# ESP32__20241002.net
KiCad netlist of a schematic drawn in Altium Designer
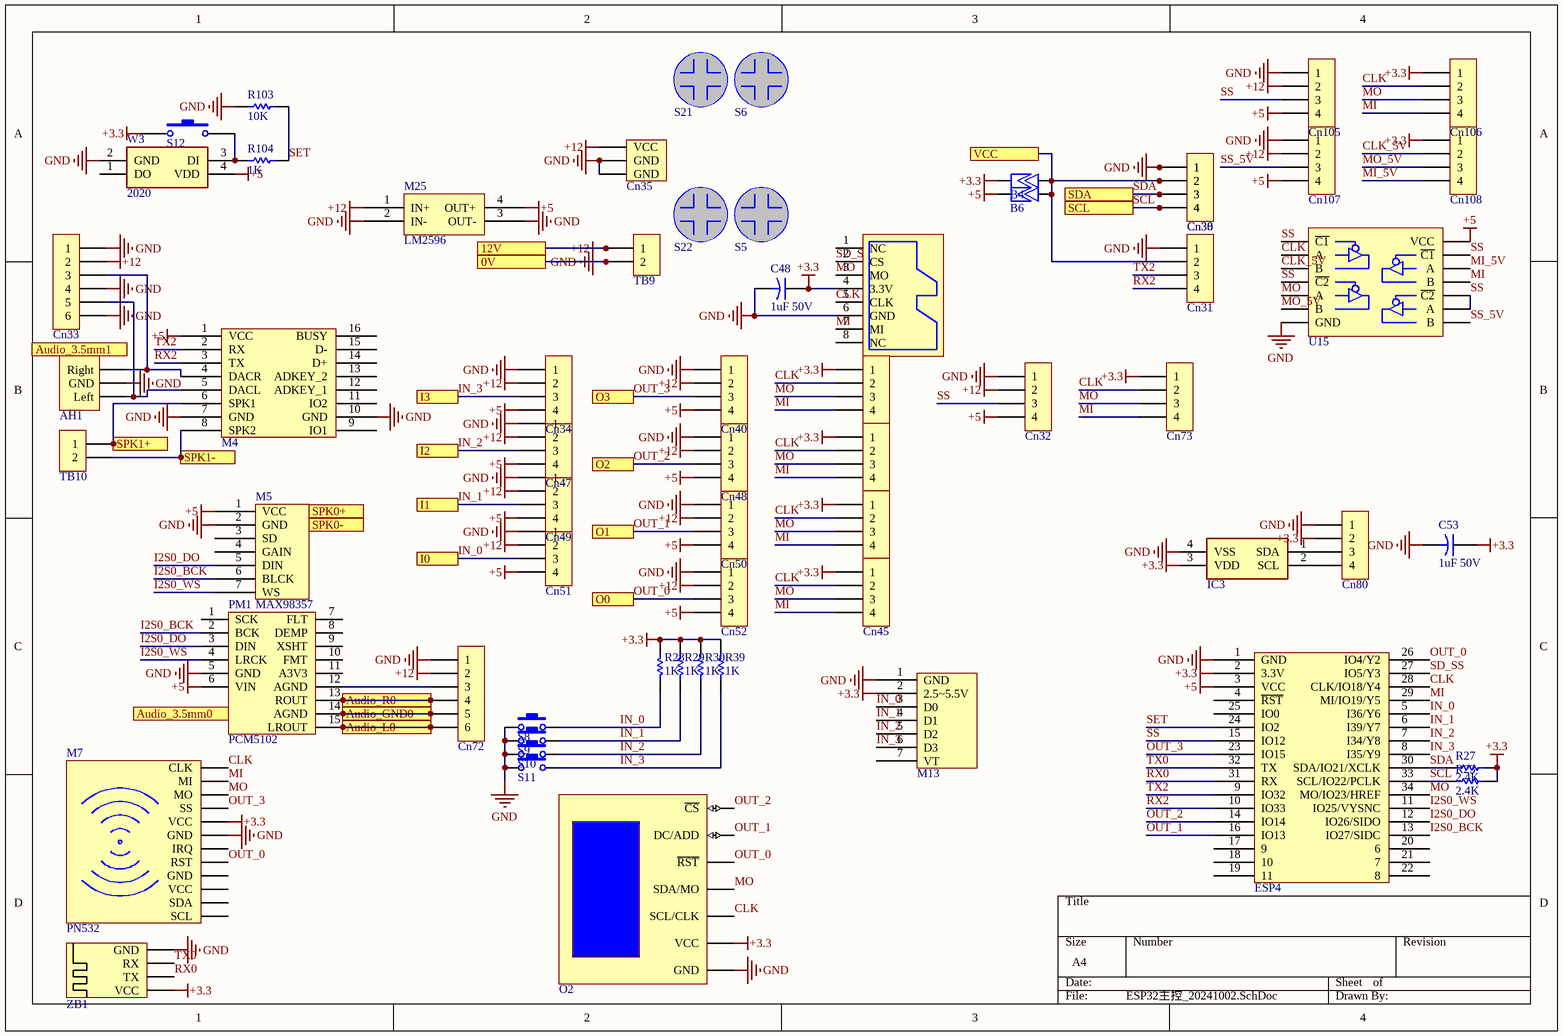
[diagram p0: ESP32主控_20241002.SchDoc]

(export (version "E")
  (design (tool "Eeschema 10.0.6"))
  (components
    (comp (ref "AH1")
      (value "Interface_Audio_hole")
      (footprint "Audio_hole_DIP")
      (description "音源孔")
      (libsource (lib "MyLibray") (part "Interface_Audio_hole"))
    )
    (comp (ref "B4")
      (value "短路")
      (footprint "BYPASS-0805")
      (description "短路焊點(如標註短路則需額外補錫使其短路)")
      (libsource (lib "MyLibray") (part "Bypass"))
    )
    (comp (ref "B6")
      (value "不短路")
      (footprint "BYPASS-0805")
      (description "短路焊點(如標註短路則需額外補錫使其短路)")
      (libsource (lib "MyLibray") (part "Bypass"))
    )
    (comp (ref "C48")
      (value "1uF 50V")
      (footprint "Cap-1206")
      (description "電容")
      (libsource (lib "MyLibray") (part "Cap"))
    )
    (comp (ref "C53")
      (value "1uF 50V")
      (footprint "Cap-1206")
      (description "電容")
      (libsource (lib "MyLibray") (part "Cap"))
    )
    (comp (ref "Cn28")
      (value "KF2510")
      (footprint "Connector_KF2510-4A")
      (description "接線端子")
      (libsource (lib "MyLibray") (part "Contact(4P)"))
    )
    (comp (ref "Cn29")
      (value "KF2510")
      (footprint "Connector_KF2510-4A")
      (description "接線端子")
      (libsource (lib "MyLibray") (part "Contact(4P)"))
    )
    (comp (ref "Cn30")
      (value "KF2510")
      (footprint "Connector_KF2510-4A")
      (description "接線端子")
      (libsource (lib "MyLibray") (part "Contact(4P)"))
    )
    (comp (ref "Cn31")
      (value "KF2510")
      (footprint "Connector_KF2510-4A")
      (description "接線端子")
      (libsource (lib "MyLibray") (part "Contact(4P)"))
    )
    (comp (ref "Cn32")
      (value "KF2510")
      (footprint "Connector_KF2510-4A")
      (description "接線端子")
      (libsource (lib "MyLibray") (part "Contact(4P)"))
    )
    (comp (ref "Cn33")
      (value "KF2510-6")
      (footprint "Connector_KF2510-6W")
      (description "接線端子")
      (libsource (lib "") (part "Contact(6P)_1"))
    )
    (comp (ref "Cn34")
      (value "KF2510")
      (footprint "Connector_KF2510-4A")
      (description "接線端子")
      (libsource (lib "MyLibray") (part "Contact(4P)"))
    )
    (comp (ref "Cn35")
      (value "DC-005")
      (footprint "Connector_DC-005")
      (description "DC直流接頭")
      (libsource (lib "MyLibray") (part "Contact_DC"))
    )
    (comp (ref "Cn38")
      (value "KF2510")
      (footprint "Connector_KF2510-4A")
      (description "接線端子")
      (libsource (lib "MyLibray") (part "Contact(4P)"))
    )
    (comp (ref "Cn40")
      (value "KF2510")
      (footprint "Connector_KF2510-4A")
      (description "接線端子")
      (libsource (lib "MyLibray") (part "Contact(4P)"))
    )
    (comp (ref "Cn43")
      (value "KF2510")
      (footprint "Connector_KF2510-4A")
      (description "接線端子")
      (libsource (lib "MyLibray") (part "Contact(4P)"))
    )
    (comp (ref "Cn45")
      (value "KF2510")
      (footprint "Connector_KF2510-4A")
      (description "接線端子")
      (libsource (lib "MyLibray") (part "Contact(4P)"))
    )
    (comp (ref "Cn47")
      (value "KF2510")
      (footprint "Connector_KF2510-4A")
      (description "接線端子")
      (libsource (lib "MyLibray") (part "Contact(4P)"))
    )
    (comp (ref "Cn48")
      (value "KF2510")
      (footprint "Connector_KF2510-4A")
      (description "接線端子")
      (libsource (lib "MyLibray") (part "Contact(4P)"))
    )
    (comp (ref "Cn49")
      (value "KF2510")
      (footprint "Connector_KF2510-4A")
      (description "接線端子")
      (libsource (lib "MyLibray") (part "Contact(4P)"))
    )
    (comp (ref "Cn50")
      (value "KF2510")
      (footprint "Connector_KF2510-4A")
      (description "接線端子")
      (libsource (lib "MyLibray") (part "Contact(4P)"))
    )
    (comp (ref "Cn51")
      (value "KF2510")
      (footprint "Connector_KF2510-4A")
      (description "接線端子")
      (libsource (lib "MyLibray") (part "Contact(4P)"))
    )
    (comp (ref "Cn52")
      (value "KF2510")
      (footprint "Connector_KF2510-4A")
      (description "接線端子")
      (libsource (lib "MyLibray") (part "Contact(4P)"))
    )
    (comp (ref "Cn72")
      (value "KF2510-6")
      (footprint "Connector_KF2510-6W")
      (description "接線端子")
      (libsource (lib "MyLibray") (part "Contact(6P)"))
    )
    (comp (ref "Cn73")
      (value "KF2510")
      (footprint "Connector_KF2510-4A")
      (description "接線端子")
      (libsource (lib "MyLibray") (part "Contact(4P)"))
    )
    (comp (ref "Cn80")
      (value "KF2510")
      (footprint "Connector_KF2510-4A")
      (description "接線端子")
      (libsource (lib "MyLibray") (part "Contact(4P)"))
    )
    (comp (ref "Cn105")
      (value "KF2510")
      (footprint "Connector_KF2510-4A")
      (description "接線端子")
      (libsource (lib "MyLibray") (part "Contact(4P)"))
    )
    (comp (ref "Cn106")
      (value "KF2510")
      (footprint "Connector_KF2510-4A")
      (description "接線端子")
      (libsource (lib "MyLibray") (part "Contact(4P)"))
    )
    (comp (ref "Cn107")
      (value "KF2510")
      (footprint "Connector_KF2510-4A")
      (description "接線端子")
      (libsource (lib "MyLibray") (part "Contact(4P)"))
    )
    (comp (ref "Cn108")
      (value "KF2510")
      (footprint "Connector_KF2510-4A")
      (description "接線端子")
      (libsource (lib "MyLibray") (part "Contact(4P)"))
    )
    (comp (ref "ESP4")
      (value "U?")
      (footprint "ESP32-WROVER-CAM Module")
      (description "WIFI通訊模組,帶OV2640攝像頭")
      (libsource (lib "MyModule") (part "ESP32-WROVER-CAM"))
    )
    (comp (ref "IC3")
      (value "SHT40")
      (footprint "Sensor_SHT40")
      (description "I2C,溫溼度感測器")
      (fields (field (name "MANUFACTURER_PART_NUMBER") "SHT40-AD1B-R3"))
      (libsource (lib "MyLibray") (part "Sensor_SHT40-AD1B-R3"))
    )
    (comp (ref "M4")
      (value "BY8001-16P")
      (footprint "BY8001-16P")
      (description "TTL通訊SD卡撥放mp3模組")
      (libsource (lib "MyModule") (part "Mini MP3 Player"))
    )
    (comp (ref "M5")
      (value "MAX98357")
      (footprint "MAX98357_Module")
      (description "I2S音頻直驅模組,3W")
      (libsource (lib "MyModule") (part "MAX98357 Module"))
    )
    (comp (ref "M7")
      (value "PN532")
      (footprint "PN532")
      (description "NFC模組")
      (libsource (lib "MyModule") (part "PN532"))
    )
    (comp (ref "M13")
      (value "XR390")
      (footprint "XR390 Module")
      (description "遙控器模組")
      (libsource (lib "MyModule") (part "XR390"))
    )
    (comp (ref "M25")
      (value "LM2596")
      (footprint "LM2596 Module")
      (description "DC to DC 降壓模組")
      (libsource (lib "MyModule") (part "LM2596"))
    )
    (comp (ref "MS4")
      (value "Interface_MicroSD card slot")
      (footprint "Interface_MicroSD card slot")
      (description "Micro SD 卡座")
      (libsource (lib "MyLibray") (part "Interface_MicroSD card slot"))
    )
    (comp (ref "O2")
      (value "0.96\"")
      (footprint "OLED-SPI/I2C")
      (description "OLED顯示模組")
      (libsource (lib "MyModule") (part "OLED_SPI/I2C"))
    )
    (comp (ref "PM1")
      (value "PCM5102")
      (footprint "PCM5102_MODULE")
      (description "I2S音頻解碼模組")
      (libsource (lib "MyModule") (part "PCM5102"))
    )
    (comp (ref "R23")
      (value "2.4K")
      (footprint "Res-1206")
      (description "電阻")
      (libsource (lib "MyLibray") (part "Res"))
    )
    (comp (ref "R27")
      (value "2.4K")
      (footprint "Res-1206")
      (description "電阻")
      (libsource (lib "MyLibray") (part "Res"))
    )
    (comp (ref "R28")
      (value "1K")
      (footprint "Res-1206")
      (description "電阻")
      (libsource (lib "MyLibray") (part "Res"))
    )
    (comp (ref "R29")
      (value "1K")
      (footprint "Res-1206")
      (description "電阻")
      (libsource (lib "MyLibray") (part "Res"))
    )
    (comp (ref "R30")
      (value "1K")
      (footprint "Res-1206")
      (description "電阻")
      (libsource (lib "MyLibray") (part "Res"))
    )
    (comp (ref "R39")
      (value "1K")
      (footprint "Res-1206")
      (description "電阻")
      (libsource (lib "MyLibray") (part "Res"))
    )
    (comp (ref "R103")
      (value "10K")
      (footprint "Res-1206")
      (description "電阻")
      (libsource (lib "MyLibray") (part "Res"))
    )
    (comp (ref "R104")
      (value "1K")
      (footprint "Res-1206")
      (description "電阻")
      (libsource (lib "MyLibray") (part "Res"))
    )
    (comp (ref "S5")
      (value "M3")
      (footprint "Screw M3")
      (description "螺絲(非焊接元件)")
      (libsource (lib "MyLibray") (part "Screw"))
    )
    (comp (ref "S6")
      (value "M3")
      (footprint "Screw M3")
      (description "螺絲(非焊接元件)")
      (libsource (lib "MyLibray") (part "Screw"))
    )
    (comp (ref "S8")
      (value "Switch")
      (footprint "Switch SMD-3.6*6*2.5")
      (description "開關_按鍵")
      (libsource (lib "MyLibray") (part "Switch"))
    )
    (comp (ref "S9")
      (value "Switch")
      (footprint "Switch SMD-3.6*6*2.5")
      (description "開關_按鍵")
      (libsource (lib "MyLibray") (part "Switch"))
    )
    (comp (ref "S10")
      (value "Switch")
      (footprint "Switch SMD-3.6*6*2.5")
      (description "開關_按鍵")
      (libsource (lib "MyLibray") (part "Switch"))
    )
    (comp (ref "S11")
      (value "Switch")
      (footprint "Switch SMD-3.6*6*2.5")
      (description "開關_按鍵")
      (libsource (lib "MyLibray") (part "Switch"))
    )
    (comp (ref "S12")
      (value "Switch")
      (footprint "Switch SMD-3.6*6*2.5")
      (description "開關_按鍵")
      (libsource (lib "") (part "Switch_1"))
    )
    (comp (ref "S21")
      (value "M3")
      (footprint "Screw M3")
      (description "螺絲(非焊接元件)")
      (libsource (lib "MyLibray") (part "Screw"))
    )
    (comp (ref "S22")
      (value "M3")
      (footprint "Screw M3")
      (description "螺絲(非焊接元件)")
      (libsource (lib "MyLibray") (part "Screw"))
    )
    (comp (ref "TB9")
      (value "ZB25(2P)")
      (footprint "Terminal block(KF2EDGR-5.08 _2P)")
      (description "端子台")
      (libsource (lib "") (part "Terminal block(2P)_1"))
    )
    (comp (ref "TB10")
      (value "ZB25(2P)")
      (footprint "Terminal block(KF2EDGR-5.08 _2P)")
      (description "端子台")
      (libsource (lib "MyLibray") (part "Terminal block(2P)"))
    )
    (comp (ref "U15")
      (value "74HC125")
      (footprint "SOP-14")
      (description "緩衝器")
      (libsource (lib "MyLibray") (part "74HC125"))
    )
    (comp (ref "W3")
      (value "2020")
      (footprint "LED-WS2812B-5050")
      (description "LED幻彩燈珠")
      (fields (field (name "MANUFACTURER_PART_NUMBER") "4684") (field (name "MOUSER PART NUMBER") "485-4684"))
      (libsource (lib "MyLibray") (part "WS2812B"))
    )
    (comp (ref "ZB1")
      (value "Zigbee")
      (footprint "ZIGBEE")
      (description "無線通訊模組")
      (libsource (lib "MyModule") (part "Zigbee"))
    )
  )
  (nets
    (net (code "1") (name "+3.3") (class "Default")
      (node (ref "B4") (pin "1") (pinfunction "1_1") (pintype "passive"))
      (node (ref "C48") (pin "1") (pinfunction "1_1") (pintype "passive"))
      (node (ref "C53") (pin "1") (pinfunction "1_1") (pintype "passive"))
      (node (ref "Cn106") (pin "1") (pinfunction "1_1") (pintype "passive"))
      (node (ref "Cn108") (pin "1") (pinfunction "1_1") (pintype "passive"))
      (node (ref "Cn28") (pin "1") (pinfunction "1_1") (pintype "passive"))
      (node (ref "Cn29") (pin "1") (pinfunction "1_1") (pintype "passive"))
      (node (ref "Cn43") (pin "1") (pinfunction "1_1") (pintype "passive"))
      (node (ref "Cn45") (pin "1") (pinfunction "1_1") (pintype "passive"))
      (node (ref "Cn73") (pin "1") (pinfunction "1_1") (pintype "passive"))
      (node (ref "Cn80") (pin "2") (pinfunction "2_2") (pintype "passive"))
      (node (ref "ESP4") (pin "2") (pinfunction "3.3V_2") (pintype "passive"))
      (node (ref "IC3") (pin "3") (pinfunction "VDD_3") (pintype "passive"))
      (node (ref "M13") (pin "2") (pinfunction "2.5~5.5V_2") (pintype "passive"))
      (node (ref "M7") (pin "5") (pinfunction "VCC_5") (pintype "passive"))
      (node (ref "MS4") (pin "4") (pinfunction "3.3V_4") (pintype "power_in"))
      (node (ref "O2") (pin "2") (pinfunction "VCC_2") (pintype "power_in"))
      (node (ref "R23") (pin "2") (pinfunction "2_2") (pintype "passive"))
      (node (ref "R27") (pin "2") (pinfunction "2_2") (pintype "passive"))
      (node (ref "R28") (pin "2") (pinfunction "2_2") (pintype "passive"))
      (node (ref "R29") (pin "2") (pinfunction "2_2") (pintype "passive"))
      (node (ref "R30") (pin "2") (pinfunction "2_2") (pintype "passive"))
      (node (ref "R39") (pin "2") (pinfunction "2_2") (pintype "passive"))
      (node (ref "S12") (pin "1") (pinfunction "1_1") (pintype "passive"))
      (node (ref "ZB1") (pin "1") (pinfunction "VCC_1") (pintype "power_in"))
    )
    (net (code "2") (name "+5") (class "Default")
      (node (ref "B6") (pin "1") (pinfunction "1_1") (pintype "passive"))
      (node (ref "Cn105") (pin "4") (pinfunction "4_4") (pintype "passive"))
      (node (ref "Cn107") (pin "4") (pinfunction "4_4") (pintype "passive"))
      (node (ref "Cn32") (pin "4") (pinfunction "4_4") (pintype "passive"))
      (node (ref "Cn34") (pin "4") (pinfunction "4_4") (pintype "passive"))
      (node (ref "Cn40") (pin "4") (pinfunction "4_4") (pintype "passive"))
      (node (ref "Cn47") (pin "4") (pinfunction "4_4") (pintype "passive"))
      (node (ref "Cn48") (pin "4") (pinfunction "4_4") (pintype "passive"))
      (node (ref "Cn49") (pin "4") (pinfunction "4_4") (pintype "passive"))
      (node (ref "Cn50") (pin "4") (pinfunction "4_4") (pintype "passive"))
      (node (ref "Cn51") (pin "4") (pinfunction "4_4") (pintype "passive"))
      (node (ref "Cn52") (pin "4") (pinfunction "4_4") (pintype "passive"))
      (node (ref "ESP4") (pin "3") (pinfunction "VCC_3") (pintype "passive"))
      (node (ref "M25") (pin "4") (pinfunction "OUT+_4") (pintype "passive"))
      (node (ref "M4") (pin "1") (pinfunction "VCC_1") (pintype "passive"))
      (node (ref "M5") (pin "1") (pinfunction "VCC_1") (pintype "passive"))
      (node (ref "PM1") (pin "6") (pinfunction "VIN_6") (pintype "passive"))
      (node (ref "U15") (pin "14") (pinfunction "VCC_14") (pintype "power_in"))
      (node (ref "W3") (pin "4") (pinfunction "VDD_4") (pintype "passive"))
    )
    (net (code "3") (name "+12") (class "Default")
      (node (ref "Cn105") (pin "2") (pinfunction "2_2") (pintype "passive"))
      (node (ref "Cn107") (pin "2") (pinfunction "2_2") (pintype "passive"))
      (node (ref "Cn32") (pin "2") (pinfunction "2_2") (pintype "passive"))
      (node (ref "Cn33") (pin "2") (pinfunction "2_2") (pintype "passive"))
      (node (ref "Cn34") (pin "2") (pinfunction "2_2") (pintype "passive"))
      (node (ref "Cn35") (pin "1") (pinfunction "VCC_1") (pintype "passive"))
      (node (ref "Cn40") (pin "2") (pinfunction "2_2") (pintype "passive"))
      (node (ref "Cn47") (pin "2") (pinfunction "2_2") (pintype "passive"))
      (node (ref "Cn48") (pin "2") (pinfunction "2_2") (pintype "passive"))
      (node (ref "Cn49") (pin "2") (pinfunction "2_2") (pintype "passive"))
      (node (ref "Cn50") (pin "2") (pinfunction "2_2") (pintype "passive"))
      (node (ref "Cn51") (pin "2") (pinfunction "2_2") (pintype "passive"))
      (node (ref "Cn52") (pin "2") (pinfunction "2_2") (pintype "passive"))
      (node (ref "Cn72") (pin "2") (pinfunction "2_2") (pintype "passive"))
      (node (ref "M25") (pin "1") (pinfunction "IN+_1") (pintype "passive"))
      (node (ref "TB9") (pin "1") (pinfunction "1_1") (pintype "passive"))
    )
    (net (code "6") (name "/Audio_GND0") (class "Default")
      (node (ref "Cn72") (pin "5") (pinfunction "5_5") (pintype "passive"))
      (node (ref "PM1") (pin "14") (pinfunction "AGND_14") (pintype "passive"))
    )
    (net (code "7") (name "/Audio_L0") (class "Default")
      (node (ref "Cn72") (pin "6") (pinfunction "6_6") (pintype "passive"))
      (node (ref "PM1") (pin "15") (pinfunction "LROUT_15") (pintype "passive"))
    )
    (net (code "8") (name "/Audio_R0") (class "Default")
      (node (ref "Cn72") (pin "4") (pinfunction "4_4") (pintype "passive"))
      (node (ref "PM1") (pin "13") (pinfunction "ROUT_13") (pintype "passive"))
    )
    (net (code "9") (name "/CLK") (class "Default")
      (node (ref "Cn106") (pin "2") (pinfunction "2_2") (pintype "passive"))
      (node (ref "Cn28") (pin "2") (pinfunction "2_2") (pintype "passive"))
      (node (ref "Cn29") (pin "2") (pinfunction "2_2") (pintype "passive"))
      (node (ref "Cn43") (pin "2") (pinfunction "2_2") (pintype "passive"))
      (node (ref "Cn45") (pin "2") (pinfunction "2_2") (pintype "passive"))
      (node (ref "Cn73") (pin "2") (pinfunction "2_2") (pintype "passive"))
      (node (ref "ESP4") (pin "28") (pinfunction "CLK/IO18/Y4_28") (pintype "passive"))
      (node (ref "M7") (pin "1") (pinfunction "CLK_1") (pintype "passive"))
      (node (ref "MS4") (pin "5") (pinfunction "CLK_5") (pintype "passive"))
      (node (ref "O2") (pin "3") (pinfunction "SCL/CLK_3") (pintype "passive"))
      (node (ref "U15") (pin "2") (pinfunction "A_2") (pintype "passive"))
    )
    (net (code "10") (name "/CLK_5V") (class "Default")
      (node (ref "Cn108") (pin "2") (pinfunction "2_2") (pintype "passive"))
      (node (ref "U15") (pin "3") (pinfunction "B_3") (pintype "passive"))
    )
    (net (code "11") (name "/I2S0_BCK") (class "Default")
      (node (ref "ESP4") (pin "13") (pinfunction "IO27/SIDC_13") (pintype "passive"))
      (node (ref "M5") (pin "6") (pinfunction "BLCK_6") (pintype "passive"))
      (node (ref "PM1") (pin "2") (pinfunction "BCK_2") (pintype "passive"))
    )
    (net (code "12") (name "/I2S0_DO") (class "Default")
      (node (ref "ESP4") (pin "12") (pinfunction "IO26/SIDO_12") (pintype "passive"))
      (node (ref "M5") (pin "5") (pinfunction "DIN_5") (pintype "passive"))
      (node (ref "PM1") (pin "3") (pinfunction "DIN_3") (pintype "passive"))
    )
    (net (code "13") (name "/I2S0_WS") (class "Default")
      (node (ref "ESP4") (pin "11") (pinfunction "IO25/VYSNC_11") (pintype "passive"))
      (node (ref "M5") (pin "7") (pinfunction "WS_7") (pintype "passive"))
      (node (ref "PM1") (pin "4") (pinfunction "LRCK_4") (pintype "passive"))
    )
    (net (code "14") (name "/IN_0") (class "Default")
      (node (ref "Cn51") (pin "3") (pinfunction "3_3") (pintype "passive"))
      (node (ref "ESP4") (pin "5") (pinfunction "I36/Y6_5") (pintype "passive"))
      (node (ref "M13") (pin "3") (pinfunction "D0_3") (pintype "passive"))
      (node (ref "R28") (pin "1") (pinfunction "1_1") (pintype "passive"))
      (node (ref "S8") (pin "2") (pinfunction "2_2") (pintype "passive"))
    )
    (net (code "15") (name "/IN_1") (class "Default")
      (node (ref "Cn49") (pin "3") (pinfunction "3_3") (pintype "passive"))
      (node (ref "ESP4") (pin "6") (pinfunction "I39/Y7_6") (pintype "passive"))
      (node (ref "M13") (pin "4") (pinfunction "D1_4") (pintype "passive"))
      (node (ref "R29") (pin "1") (pinfunction "1_1") (pintype "passive"))
      (node (ref "S9") (pin "2") (pinfunction "2_2") (pintype "passive"))
    )
    (net (code "16") (name "/IN_2") (class "Default")
      (node (ref "Cn47") (pin "3") (pinfunction "3_3") (pintype "passive"))
      (node (ref "ESP4") (pin "7") (pinfunction "I34/Y8_7") (pintype "passive"))
      (node (ref "M13") (pin "5") (pinfunction "D2_5") (pintype "passive"))
      (node (ref "R30") (pin "1") (pinfunction "1_1") (pintype "passive"))
      (node (ref "S10") (pin "2") (pinfunction "2_2") (pintype "passive"))
    )
    (net (code "17") (name "/IN_3") (class "Default")
      (node (ref "Cn34") (pin "3") (pinfunction "3_3") (pintype "passive"))
      (node (ref "ESP4") (pin "8") (pinfunction "I35/Y9_8") (pintype "passive"))
      (node (ref "M13") (pin "6") (pinfunction "D3_6") (pintype "passive"))
      (node (ref "R39") (pin "1") (pinfunction "1_1") (pintype "passive"))
      (node (ref "S11") (pin "2") (pinfunction "2_2") (pintype "passive"))
    )
    (net (code "18") (name "/MI") (class "Default")
      (node (ref "Cn106") (pin "4") (pinfunction "4_4") (pintype "passive"))
      (node (ref "Cn28") (pin "4") (pinfunction "4_4") (pintype "passive"))
      (node (ref "Cn29") (pin "4") (pinfunction "4_4") (pintype "passive"))
      (node (ref "Cn43") (pin "4") (pinfunction "4_4") (pintype "passive"))
      (node (ref "Cn45") (pin "4") (pinfunction "4_4") (pintype "passive"))
      (node (ref "Cn73") (pin "4") (pinfunction "4_4") (pintype "passive"))
      (node (ref "ESP4") (pin "29") (pinfunction "MI/IO19/Y5_29") (pintype "passive"))
      (node (ref "M7") (pin "2") (pinfunction "MI_2") (pintype "passive"))
      (node (ref "MS4") (pin "7") (pinfunction "MI_7") (pintype "passive"))
      (node (ref "U15") (pin "11") (pinfunction "B_11") (pintype "passive"))
    )
    (net (code "19") (name "/MI_5V") (class "Default")
      (node (ref "Cn108") (pin "4") (pinfunction "4_4") (pintype "passive"))
      (node (ref "U15") (pin "12") (pinfunction "A_12") (pintype "passive"))
    )
    (net (code "20") (name "/MO") (class "Default")
      (node (ref "Cn106") (pin "3") (pinfunction "3_3") (pintype "passive"))
      (node (ref "Cn28") (pin "3") (pinfunction "3_3") (pintype "passive"))
      (node (ref "Cn29") (pin "3") (pinfunction "3_3") (pintype "passive"))
      (node (ref "Cn43") (pin "3") (pinfunction "3_3") (pintype "passive"))
      (node (ref "Cn45") (pin "3") (pinfunction "3_3") (pintype "passive"))
      (node (ref "Cn73") (pin "3") (pinfunction "3_3") (pintype "passive"))
      (node (ref "ESP4") (pin "34") (pinfunction "MO/IO23/HREF_34") (pintype "passive"))
      (node (ref "M7") (pin "3") (pinfunction "MO_3") (pintype "passive"))
      (node (ref "MS4") (pin "3") (pinfunction "MO_3") (pintype "passive"))
      (node (ref "O2") (pin "4") (pinfunction "SDA/MO_4") (pintype "passive"))
      (node (ref "U15") (pin "5") (pinfunction "A_5") (pintype "passive"))
    )
    (net (code "21") (name "/MO_5V") (class "Default")
      (node (ref "Cn108") (pin "3") (pinfunction "3_3") (pintype "passive"))
      (node (ref "U15") (pin "6") (pinfunction "B_6") (pintype "passive"))
    )
    (net (code "22") (name "/OUT_0") (class "Default")
      (node (ref "Cn52") (pin "3") (pinfunction "3_3") (pintype "passive"))
      (node (ref "ESP4") (pin "26") (pinfunction "IO4/Y2_26") (pintype "passive"))
      (node (ref "M7") (pin "8") (pinfunction "RST_8") (pintype "passive"))
      (node (ref "O2") (pin "5") (pinfunction "~{RST}_5") (pintype "passive"))
    )
    (net (code "23") (name "/OUT_1") (class "Default")
      (node (ref "Cn50") (pin "3") (pinfunction "3_3") (pintype "passive"))
      (node (ref "ESP4") (pin "16") (pinfunction "IO13_16") (pintype "passive"))
      (node (ref "O2") (pin "6") (pinfunction "DC/ADD_6") (pintype "bidirectional"))
    )
    (net (code "24") (name "/OUT_2") (class "Default")
      (node (ref "Cn48") (pin "3") (pinfunction "3_3") (pintype "passive"))
      (node (ref "ESP4") (pin "14") (pinfunction "IO14_14") (pintype "passive"))
      (node (ref "O2") (pin "7") (pinfunction "~{CS}_7") (pintype "bidirectional"))
    )
    (net (code "25") (name "/OUT_3") (class "Default")
      (node (ref "Cn40") (pin "3") (pinfunction "3_3") (pintype "passive"))
      (node (ref "ESP4") (pin "23") (pinfunction "IO15_23") (pintype "passive"))
      (node (ref "M7") (pin "4") (pinfunction "SS_4") (pintype "passive"))
    )
    (net (code "26") (name "/RX0") (class "Default")
      (node (ref "ESP4") (pin "31") (pinfunction "RX_31") (pintype "passive"))
      (node (ref "ZB1") (pin "2") (pinfunction "TX_2") (pintype "passive"))
    )
    (net (code "27") (name "/RX2") (class "Default")
      (node (ref "Cn31") (pin "4") (pinfunction "4_4") (pintype "passive"))
      (node (ref "ESP4") (pin "10") (pinfunction "IO33_10") (pintype "passive"))
      (node (ref "M4") (pin "3") (pinfunction "TX_3") (pintype "passive"))
    )
    (net (code "28") (name "/SCL") (class "Default")
      (node (ref "Cn30") (pin "4") (pinfunction "4_4") (pintype "passive"))
      (node (ref "Cn38") (pin "4") (pinfunction "4_4") (pintype "passive"))
      (node (ref "ESP4") (pin "33") (pinfunction "SCL/IO22/PCLK_33") (pintype "passive"))
      (node (ref "R23") (pin "1") (pinfunction "1_1") (pintype "passive"))
    )
    (net (code "29") (name "/SDA") (class "Default")
      (node (ref "Cn30") (pin "3") (pinfunction "3_3") (pintype "passive"))
      (node (ref "Cn38") (pin "3") (pinfunction "3_3") (pintype "passive"))
      (node (ref "ESP4") (pin "30") (pinfunction "SDA/IO21/XCLK_30") (pintype "passive"))
      (node (ref "R27") (pin "1") (pinfunction "1_1") (pintype "passive"))
    )
    (net (code "30") (name "/SD_SS") (class "Default")
      (node (ref "ESP4") (pin "27") (pinfunction "IO5/Y3_27") (pintype "passive"))
      (node (ref "MS4") (pin "2") (pinfunction "CS_2") (pintype "passive"))
    )
    (net (code "31") (name "/SET") (class "Default")
      (node (ref "ESP4") (pin "24") (pinfunction "IO2_24") (pintype "passive"))
      (node (ref "R103") (pin "2") (pinfunction "2_2") (pintype "passive"))
      (node (ref "R104") (pin "2") (pinfunction "2_2") (pintype "passive"))
    )
    (net (code "34") (name "/SPK1+") (class "Default")
      (node (ref "M4") (pin "6") (pinfunction "SPK1_6") (pintype "passive"))
      (node (ref "TB10") (pin "1") (pinfunction "1_1") (pintype "passive"))
    )
    (net (code "35") (name "/SPK1-") (class "Default")
      (node (ref "M4") (pin "8") (pinfunction "SPK2_8") (pintype "passive"))
      (node (ref "TB10") (pin "2") (pinfunction "2_2") (pintype "passive"))
    )
    (net (code "36") (name "/SS") (class "Default")
      (node (ref "Cn105") (pin "3") (pinfunction "3_3") (pintype "passive"))
      (node (ref "Cn32") (pin "3") (pinfunction "3_3") (pintype "passive"))
      (node (ref "ESP4") (pin "15") (pinfunction "IO12_15") (pintype "passive"))
      (node (ref "U15") (pin "1") (pinfunction "~{C1}_1") (pintype "passive"))
      (node (ref "U15") (pin "10") (pinfunction "~{C2}_10") (pintype "passive"))
      (node (ref "U15") (pin "13") (pinfunction "~{C1}_13") (pintype "passive"))
      (node (ref "U15") (pin "4") (pinfunction "~{C2}_4") (pintype "passive"))
      (node (ref "U15") (pin "9") (pinfunction "A_9") (pintype "passive"))
    )
    (net (code "37") (name "/SS_5V") (class "Default")
      (node (ref "Cn107") (pin "3") (pinfunction "3_3") (pintype "passive"))
      (node (ref "U15") (pin "8") (pinfunction "B_8") (pintype "passive"))
    )
    (net (code "38") (name "/TX0") (class "Default")
      (node (ref "ESP4") (pin "32") (pinfunction "TX_32") (pintype "passive"))
      (node (ref "ZB1") (pin "3") (pinfunction "RX_3") (pintype "passive"))
    )
    (net (code "39") (name "/TX2") (class "Default")
      (node (ref "Cn31") (pin "3") (pinfunction "3_3") (pintype "passive"))
      (node (ref "ESP4") (pin "9") (pinfunction "IO32_9") (pintype "passive"))
      (node (ref "M4") (pin "2") (pinfunction "RX_2") (pintype "passive"))
    )
    (net (code "40") (name "/VCC") (class "Default")
      (node (ref "B4") (pin "2") (pinfunction "2_2") (pintype "passive"))
      (node (ref "B6") (pin "2") (pinfunction "2_2") (pintype "passive"))
      (node (ref "Cn30") (pin "2") (pinfunction "2_2") (pintype "passive"))
      (node (ref "Cn31") (pin "2") (pinfunction "2_2") (pintype "passive"))
      (node (ref "Cn38") (pin "2") (pinfunction "2_2") (pintype "passive"))
    )
    (net (code "41") (name "GND") (class "Default")
      (node (ref "AH1") (pin "1") (pinfunction "GND_1") (pintype "power_in"))
      (node (ref "C48") (pin "2") (pinfunction "2_2") (pintype "passive"))
      (node (ref "C53") (pin "2") (pinfunction "2_2") (pintype "passive"))
      (node (ref "Cn105") (pin "1") (pinfunction "1_1") (pintype "passive"))
      (node (ref "Cn107") (pin "1") (pinfunction "1_1") (pintype "passive"))
      (node (ref "Cn30") (pin "1") (pinfunction "1_1") (pintype "passive"))
      (node (ref "Cn31") (pin "1") (pinfunction "1_1") (pintype "passive"))
      (node (ref "Cn32") (pin "1") (pinfunction "1_1") (pintype "passive"))
      (node (ref "Cn33") (pin "1") (pinfunction "1_1") (pintype "passive"))
      (node (ref "Cn33") (pin "4") (pinfunction "4_4") (pintype "passive"))
      (node (ref "Cn33") (pin "6") (pinfunction "6_6") (pintype "passive"))
      (node (ref "Cn34") (pin "1") (pinfunction "1_1") (pintype "passive"))
      (node (ref "Cn35") (pin "2") (pinfunction "GND_2") (pintype "passive"))
      (node (ref "Cn35") (pin "3") (pinfunction "GND_3") (pintype "passive"))
      (node (ref "Cn38") (pin "1") (pinfunction "1_1") (pintype "passive"))
      (node (ref "Cn40") (pin "1") (pinfunction "1_1") (pintype "passive"))
      (node (ref "Cn47") (pin "1") (pinfunction "1_1") (pintype "passive"))
      (node (ref "Cn48") (pin "1") (pinfunction "1_1") (pintype "passive"))
      (node (ref "Cn49") (pin "1") (pinfunction "1_1") (pintype "passive"))
      (node (ref "Cn50") (pin "1") (pinfunction "1_1") (pintype "passive"))
      (node (ref "Cn51") (pin "1") (pinfunction "1_1") (pintype "passive"))
      (node (ref "Cn52") (pin "1") (pinfunction "1_1") (pintype "passive"))
      (node (ref "Cn72") (pin "1") (pinfunction "1_1") (pintype "passive"))
      (node (ref "Cn80") (pin "1") (pinfunction "1_1") (pintype "passive"))
      (node (ref "ESP4") (pin "1") (pinfunction "GND_1") (pintype "passive"))
      (node (ref "IC3") (pin "4") (pinfunction "VSS_4") (pintype "passive"))
      (node (ref "M13") (pin "1") (pinfunction "GND_1") (pintype "passive"))
      (node (ref "M25") (pin "2") (pinfunction "IN-_2") (pintype "passive"))
      (node (ref "M25") (pin "3") (pinfunction "OUT-_3") (pintype "passive"))
      (node (ref "M4") (pin "10") (pinfunction "GND_10") (pintype "passive"))
      (node (ref "M4") (pin "7") (pinfunction "GND_7") (pintype "passive"))
      (node (ref "M5") (pin "2") (pinfunction "GND_2") (pintype "passive"))
      (node (ref "M7") (pin "6") (pinfunction "GND_6") (pintype "passive"))
      (node (ref "MS4") (pin "6") (pinfunction "GND_6") (pintype "power_in"))
      (node (ref "O2") (pin "1") (pinfunction "GND_1") (pintype "power_in"))
      (node (ref "PM1") (pin "5") (pinfunction "GND_5") (pintype "passive"))
      (node (ref "R103") (pin "1") (pinfunction "1_1") (pintype "passive"))
      (node (ref "S10") (pin "1") (pinfunction "1_1") (pintype "passive"))
      (node (ref "S11") (pin "1") (pinfunction "1_1") (pintype "passive"))
      (node (ref "S8") (pin "1") (pinfunction "1_1") (pintype "passive"))
      (node (ref "S9") (pin "1") (pinfunction "1_1") (pintype "passive"))
      (node (ref "TB9") (pin "2") (pinfunction "2_2") (pintype "passive"))
      (node (ref "U15") (pin "7") (pinfunction "GND_7") (pintype "power_in"))
      (node (ref "W3") (pin "2") (pinfunction "GND_2") (pintype "passive"))
      (node (ref "ZB1") (pin "4") (pinfunction "GND_4") (pintype "power_in"))
    )
    (net (code "42") (name "Net-(AH1-Left)") (class "Default")
      (node (ref "AH1") (pin "2") (pinfunction "Left_2") (pintype "passive"))
      (node (ref "Cn33") (pin "5") (pinfunction "5_5") (pintype "passive"))
      (node (ref "M4") (pin "5") (pinfunction "DACL_5") (pintype "passive"))
    )
    (net (code "43") (name "Net-(AH1-Right)") (class "Default")
      (node (ref "AH1") (pin "3") (pinfunction "Right_3") (pintype "passive"))
      (node (ref "Cn33") (pin "3") (pinfunction "3_3") (pintype "passive"))
      (node (ref "M4") (pin "4") (pinfunction "DACR_4") (pintype "passive"))
    )
    (net (code "44") (name "Net-(Cn72-Pad3)") (class "Default")
      (node (ref "Cn72") (pin "3") (pinfunction "3_3") (pintype "passive"))
      (node (ref "PM1") (pin "12") (pinfunction "AGND_12") (pintype "passive"))
    )
    (net (code "45") (name "Net-(IC3-SCL)") (class "Default")
      (node (ref "Cn80") (pin "4") (pinfunction "4_4") (pintype "passive"))
      (node (ref "IC3") (pin "2") (pinfunction "SCL_2") (pintype "passive"))
    )
    (net (code "46") (name "Net-(IC3-SDA)") (class "Default")
      (node (ref "Cn80") (pin "3") (pinfunction "3_3") (pintype "passive"))
      (node (ref "IC3") (pin "1") (pinfunction "SDA_1") (pintype "passive"))
    )
    (net (code "47") (name "Net-(W3-DI)") (class "Default")
      (node (ref "R104") (pin "1") (pinfunction "1_1") (pintype "passive"))
      (node (ref "S12") (pin "2") (pinfunction "2_2") (pintype "passive"))
      (node (ref "W3") (pin "3") (pinfunction "DI_3") (pintype "passive"))
    )
    (net (code "48") (name "unconnected-(ESP4-6-Pad20)") (class "Default")
      (node (ref "ESP4") (pin "20") (pinfunction "6_20") (pintype "passive"))
    )
    (net (code "49") (name "unconnected-(ESP4-7-Pad21)") (class "Default")
      (node (ref "ESP4") (pin "21") (pinfunction "7_21") (pintype "passive"))
    )
    (net (code "50") (name "unconnected-(ESP4-8-Pad22)") (class "Default")
      (node (ref "ESP4") (pin "22") (pinfunction "8_22") (pintype "passive"))
    )
    (net (code "51") (name "unconnected-(ESP4-9-Pad17)") (class "Default")
      (node (ref "ESP4") (pin "17") (pinfunction "9_17") (pintype "passive"))
    )
    (net (code "52") (name "unconnected-(ESP4-10-Pad18)") (class "Default")
      (node (ref "ESP4") (pin "18") (pinfunction "10_18") (pintype "passive"))
    )
    (net (code "53") (name "unconnected-(ESP4-11-Pad19)") (class "Default")
      (node (ref "ESP4") (pin "19") (pinfunction "11_19") (pintype "passive"))
    )
    (net (code "54") (name "unconnected-(ESP4-IO0-Pad25)") (class "Default")
      (node (ref "ESP4") (pin "25") (pinfunction "IO0_25") (pintype "passive"))
    )
    (net (code "55") (name "unconnected-(ESP4-~{RST}-Pad4)") (class "Default")
      (node (ref "ESP4") (pin "4") (pinfunction "~{RST}_4") (pintype "passive"))
    )
    (net (code "56") (name "unconnected-(M4-ADKEY_1-Pad12)") (class "Default")
      (node (ref "M4") (pin "12") (pinfunction "ADKEY_1_12") (pintype "passive"))
    )
    (net (code "57") (name "unconnected-(M4-ADKEY_2-Pad13)") (class "Default")
      (node (ref "M4") (pin "13") (pinfunction "ADKEY_2_13") (pintype "passive"))
    )
    (net (code "58") (name "unconnected-(M4-BUSY-Pad16)") (class "Default")
      (node (ref "M4") (pin "16") (pinfunction "BUSY_16") (pintype "passive"))
    )
    (net (code "59") (name "unconnected-(M4-D+-Pad14)") (class "Default")
      (node (ref "M4") (pin "14") (pinfunction "D+_14") (pintype "passive"))
    )
    (net (code "60") (name "unconnected-(M4-D--Pad15)") (class "Default")
      (node (ref "M4") (pin "15") (pinfunction "D-_15") (pintype "passive"))
    )
    (net (code "61") (name "unconnected-(M4-IO1-Pad9)") (class "Default")
      (node (ref "M4") (pin "9") (pinfunction "IO1_9") (pintype "passive"))
    )
    (net (code "62") (name "unconnected-(M4-IO2-Pad11)") (class "Default")
      (node (ref "M4") (pin "11") (pinfunction "IO2_11") (pintype "passive"))
    )
    (net (code "63") (name "unconnected-(M5-GAIN-Pad4)") (class "Default")
      (node (ref "M5") (pin "4") (pinfunction "GAIN_4") (pintype "passive"))
    )
    (net (code "64") (name "unconnected-(M5-SD-Pad3)") (class "Default")
      (node (ref "M5") (pin "3") (pinfunction "SD_3") (pintype "passive"))
    )
    (net (code "65") (name "unconnected-(M7-GND-Pad9)") (class "Default")
      (node (ref "M7") (pin "9") (pinfunction "GND_9") (pintype "passive"))
    )
    (net (code "66") (name "unconnected-(M7-IRQ-Pad7)") (class "Default")
      (node (ref "M7") (pin "7") (pinfunction "IRQ_7") (pintype "passive"))
    )
    (net (code "67") (name "unconnected-(M7-SCL-Pad12)") (class "Default")
      (node (ref "M7") (pin "12") (pinfunction "SCL_12") (pintype "passive"))
    )
    (net (code "68") (name "unconnected-(M7-SDA-Pad11)") (class "Default")
      (node (ref "M7") (pin "11") (pinfunction "SDA_11") (pintype "passive"))
    )
    (net (code "69") (name "unconnected-(M7-VCC-Pad10)") (class "Default")
      (node (ref "M7") (pin "10") (pinfunction "VCC_10") (pintype "passive"))
    )
    (net (code "70") (name "unconnected-(M13-VT-Pad7)") (class "Default")
      (node (ref "M13") (pin "7") (pinfunction "VT_7") (pintype "passive"))
    )
    (net (code "71") (name "unconnected-(MS4-NC-Pad1)") (class "Default")
      (node (ref "MS4") (pin "1") (pinfunction "NC_1") (pintype "passive"))
    )
    (net (code "72") (name "unconnected-(MS4-NC-Pad8)") (class "Default")
      (node (ref "MS4") (pin "8") (pinfunction "NC_8") (pintype "passive"))
    )
    (net (code "73") (name "unconnected-(PM1-A3V3-Pad11)") (class "Default")
      (node (ref "PM1") (pin "11") (pinfunction "A3V3_11") (pintype "passive"))
    )
    (net (code "74") (name "unconnected-(PM1-DEMP-Pad8)") (class "Default")
      (node (ref "PM1") (pin "8") (pinfunction "DEMP_8") (pintype "passive"))
    )
    (net (code "75") (name "unconnected-(PM1-FLT-Pad7)") (class "Default")
      (node (ref "PM1") (pin "7") (pinfunction "FLT_7") (pintype "passive"))
    )
    (net (code "76") (name "unconnected-(PM1-FMT-Pad10)") (class "Default")
      (node (ref "PM1") (pin "10") (pinfunction "FMT_10") (pintype "passive"))
    )
    (net (code "77") (name "unconnected-(PM1-SCK-Pad1)") (class "Default")
      (node (ref "PM1") (pin "1") (pinfunction "SCK_1") (pintype "passive"))
    )
    (net (code "78") (name "unconnected-(PM1-XSHT-Pad9)") (class "Default")
      (node (ref "PM1") (pin "9") (pinfunction "XSHT_9") (pintype "passive"))
    )
    (net (code "79") (name "unconnected-(W3-DO-Pad1)") (class "Default")
      (node (ref "W3") (pin "1") (pinfunction "DO_1") (pintype "passive"))
    )
  )
)
